# robber_v02.net
KiCad netlist of a schematic drawn in EAGLE
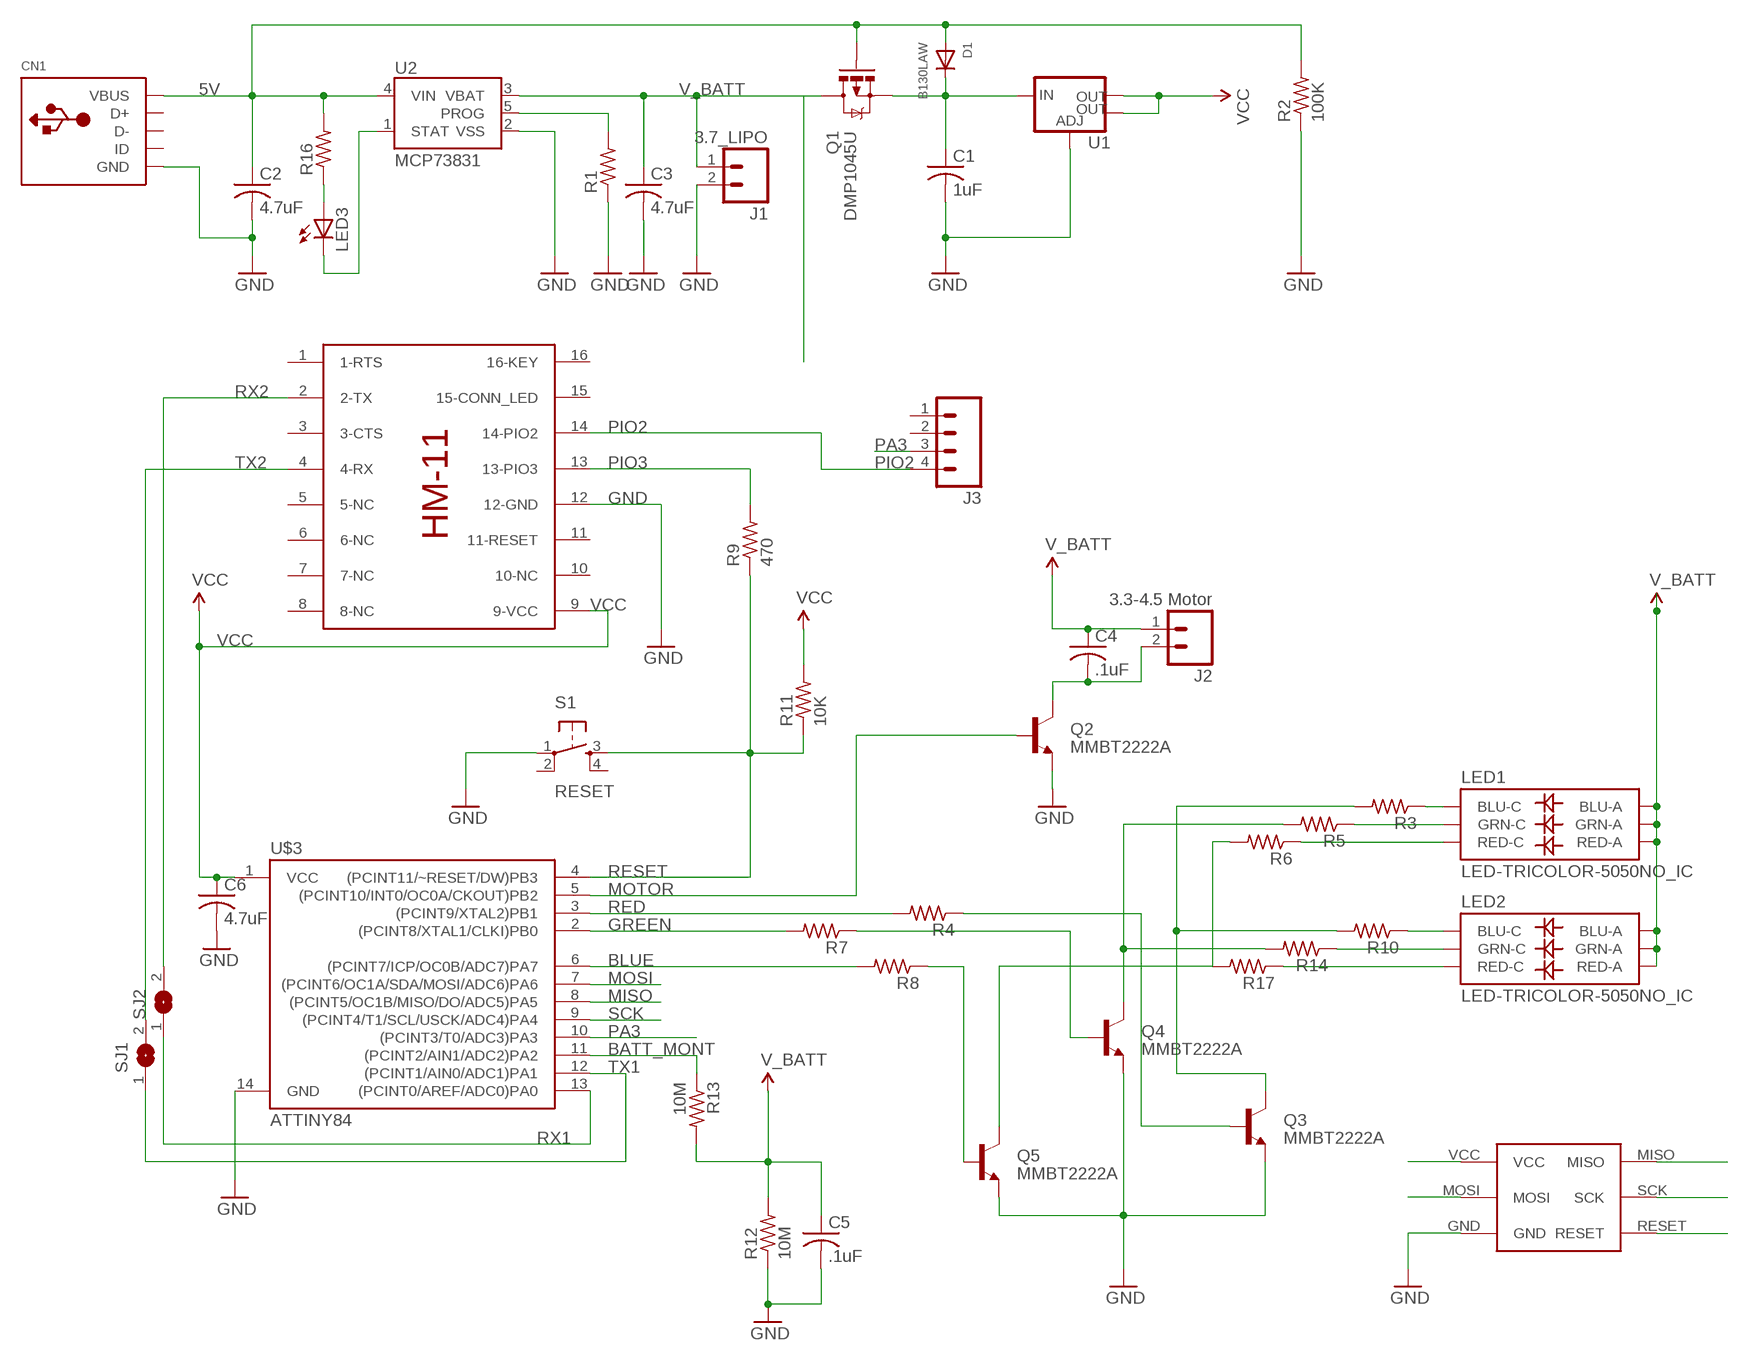
[diagram p0: schematic, sheet 1]

(export (version "E")
  (design (tool "Eeschema 10.0.6"))
  (components
    (comp (ref "C1")
      (value "1uF")
      (footprint "eagle-import:C0805K")
      (libsource (lib "eagle-import") (part "C-USC0805K"))
    )
    (comp (ref "C2")
      (value "4.7uF")
      (footprint "eagle-import:C0805K")
      (libsource (lib "eagle-import") (part "C-USC0805K"))
    )
    (comp (ref "C3")
      (value "4.7uF")
      (footprint "eagle-import:C0805")
      (libsource (lib "eagle-import") (part "C-USC0805"))
    )
    (comp (ref "C4")
      (value ".1uF")
      (footprint "eagle-import:C0402K")
      (libsource (lib "eagle-import") (part "C-USC0402K"))
    )
    (comp (ref "C5")
      (value ".1uF")
      (footprint "eagle-import:C0805")
      (libsource (lib "eagle-import") (part "C-USC0805"))
    )
    (comp (ref "C6")
      (value "4.7uF")
      (footprint "eagle-import:C0805")
      (libsource (lib "eagle-import") (part "C-USC0805"))
    )
    (comp (ref "CN1")
      (value "USBMINIB")
      (footprint "eagle-import:USB-MINIB")
      (libsource (lib "eagle-import") (part "USBMINIB"))
    )
    (comp (ref "D1")
      (value "B130LAW")
      (footprint "eagle-import:SOD-123")
      (libsource (lib "eagle-import") (part "DIODESOD-123"))
    )
    (comp (ref "J1")
      (value "3.7_LIPO")
      (footprint "eagle-import:1X02")
      (libsource (lib "eagle-import") (part "M02PTH"))
    )
    (comp (ref "J2")
      (value "3.3-4.5 Motor")
      (footprint "eagle-import:1X02")
      (libsource (lib "eagle-import") (part "M02PTH"))
    )
    (comp (ref "J3")
      (value "M04PTH")
      (footprint "eagle-import:1X04")
      (libsource (lib "eagle-import") (part "M04PTH"))
    )
    (comp (ref "LED1")
      (value "LED-TRICOLOR-5050NO_IC")
      (footprint "eagle-import:LED-TRICOLOR-5050")
      (libsource (lib "eagle-import") (part "LED-TRICOLOR-5050NO_IC"))
    )
    (comp (ref "LED2")
      (value "LED-TRICOLOR-5050NO_IC")
      (footprint "eagle-import:LED-TRICOLOR-5050")
      (libsource (lib "eagle-import") (part "LED-TRICOLOR-5050NO_IC"))
    )
    (comp (ref "LED3")
      (value "LEDSML0603")
      (footprint "eagle-import:SML0603")
      (libsource (lib "eagle-import") (part "LEDSML0603"))
    )
    (comp (ref "Q1")
      (value "DMP1045U")
      (footprint "eagle-import:SOT23-3")
      (libsource (lib "eagle-import") (part "MOSFET-PCHANNEL"))
    )
    (comp (ref "Q2")
      (value "MMBT2222A")
      (footprint "eagle-import:SOT23-3")
      (libsource (lib "eagle-import") (part "TRANSISTOR_NPNMMBT2222A"))
    )
    (comp (ref "Q3")
      (value "MMBT2222A")
      (footprint "eagle-import:SOT23-3")
      (libsource (lib "eagle-import") (part "TRANSISTOR_NPNMMBT2222A"))
    )
    (comp (ref "Q4")
      (value "MMBT2222A")
      (footprint "eagle-import:SOT23-3")
      (libsource (lib "eagle-import") (part "TRANSISTOR_NPNMMBT2222A"))
    )
    (comp (ref "Q5")
      (value "MMBT2222A")
      (footprint "eagle-import:SOT23-3")
      (libsource (lib "eagle-import") (part "TRANSISTOR_NPNMMBT2222A"))
    )
    (comp (ref "R1")
      (value "R-US_R0805W")
      (footprint "eagle-import:R0805W")
      (libsource (lib "eagle-import") (part "R-US_R0805W"))
    )
    (comp (ref "R2")
      (value "100K")
      (footprint "eagle-import:R0805W")
      (libsource (lib "eagle-import") (part "R-US_R0805W"))
    )
    (comp (ref "R3")
      (value "R-US_R0402")
      (footprint "eagle-import:R0402")
      (libsource (lib "eagle-import") (part "R-US_R0402"))
    )
    (comp (ref "R4")
      (value "R-US_R0402")
      (footprint "eagle-import:R0402")
      (libsource (lib "eagle-import") (part "R-US_R0402"))
    )
    (comp (ref "R5")
      (value "R-US_R0402")
      (footprint "eagle-import:R0402")
      (libsource (lib "eagle-import") (part "R-US_R0402"))
    )
    (comp (ref "R6")
      (value "R-US_R0402")
      (footprint "eagle-import:R0402")
      (libsource (lib "eagle-import") (part "R-US_R0402"))
    )
    (comp (ref "R7")
      (value "R-US_R0402")
      (footprint "eagle-import:R0402")
      (libsource (lib "eagle-import") (part "R-US_R0402"))
    )
    (comp (ref "R8")
      (value "R-US_R0402")
      (footprint "eagle-import:R0402")
      (libsource (lib "eagle-import") (part "R-US_R0402"))
    )
    (comp (ref "R9")
      (value "470")
      (footprint "eagle-import:R0805")
      (libsource (lib "eagle-import") (part "R-US_R0805"))
    )
    (comp (ref "R10")
      (value "R-US_R0402")
      (footprint "eagle-import:R0402")
      (libsource (lib "eagle-import") (part "R-US_R0402"))
    )
    (comp (ref "R11")
      (value "10K")
      (footprint "eagle-import:R0805W")
      (libsource (lib "eagle-import") (part "R-US_R0805W"))
    )
    (comp (ref "R12")
      (value "10M")
      (footprint "eagle-import:R0805W")
      (libsource (lib "eagle-import") (part "R-US_R0805W"))
    )
    (comp (ref "R13")
      (value "10M")
      (footprint "eagle-import:R0805W")
      (libsource (lib "eagle-import") (part "R-US_R0805W"))
    )
    (comp (ref "R14")
      (value "R-US_R0402")
      (footprint "eagle-import:R0402")
      (libsource (lib "eagle-import") (part "R-US_R0402"))
    )
    (comp (ref "R16")
      (value "R-US_R0805W")
      (footprint "eagle-import:R0805W")
      (libsource (lib "eagle-import") (part "R-US_R0805W"))
    )
    (comp (ref "R17")
      (value "R-US_R0402")
      (footprint "eagle-import:R0402")
      (libsource (lib "eagle-import") (part "R-US_R0402"))
    )
    (comp (ref "S1")
      (value "RESET")
      (footprint "eagle-import:TACTILE-SWITCH-SMD")
      (libsource (lib "eagle-import") (part "TAC_SWITCHSMD"))
    )
    (comp (ref "SJ1") (value "SJ") (footprint "eagle-import:SJ") (libsource (lib "eagle-import") (part "SJ")))
    (comp (ref "SJ2") (value "SJ") (footprint "eagle-import:SJ") (libsource (lib "eagle-import") (part "SJ")))
    (comp (ref "U$1")
      (value "HM-11")
      (footprint "eagle-import:HM-11")
      (libsource (lib "eagle-import") (part "HM-11"))
    )
    (comp (ref "U$3")
      (value "ATTINY84")
      (footprint "eagle-import:SO14")
      (libsource (lib "eagle-import") (part "ATTINY84"))
    )
    (comp (ref "U$5")
      (value "TINY-AVR-POGO-PIN-KEY")
      (footprint "eagle-import:TINY-AVR-POGO-PIN-KEY")
      (libsource (lib "eagle-import") (part "TINY-AVR-POGO-PIN-KEY"))
    )
    (comp (ref "U1")
      (value "V_REG_LM1117SOT223")
      (footprint "eagle-import:SOT223")
      (libsource (lib "eagle-import") (part "V_REG_LM1117SOT223"))
    )
    (comp (ref "U2")
      (value "MCP73831")
      (footprint "eagle-import:SOT23-5")
      (libsource (lib "eagle-import") (part "MCP73831"))
    )
  )
  (nets
    (net (code "1") (name "/5V") (class "Default")
      (node (ref "C2") (pin "1") (pinfunction "1_1") (pintype "passive"))
      (node (ref "CN1") (pin "VBUS") (pinfunction "VBUS_VBUS") (pintype "power_in"))
      (node (ref "D1") (pin "A") (pinfunction "A_A") (pintype "passive"))
      (node (ref "Q1") (pin "1") (pinfunction "G_1") (pintype "passive"))
      (node (ref "R16") (pin "2") (pinfunction "2_2") (pintype "passive"))
      (node (ref "R2") (pin "2") (pinfunction "2_2") (pintype "passive"))
      (node (ref "U2") (pin "4") (pinfunction "VIN_4") (pintype "power_in"))
    )
    (net (code "2") (name "/BATT_MONT") (class "Default")
      (node (ref "R13") (pin "1") (pinfunction "1_1") (pintype "passive"))
      (node (ref "U$3") (pin "11") (pinfunction "(PCINT2/AIN1/ADC2)PA2_11") (pintype "bidirectional"))
    )
    (net (code "3") (name "/BLUE") (class "Default")
      (node (ref "R8") (pin "2") (pinfunction "2_2") (pintype "passive"))
      (node (ref "U$3") (pin "6") (pinfunction "(PCINT7/ICP/OC0B/ADC7)PA7_6") (pintype "bidirectional"))
    )
    (net (code "4") (name "/GREEN") (class "Default")
      (node (ref "R7") (pin "2") (pinfunction "2_2") (pintype "passive"))
      (node (ref "U$3") (pin "2") (pinfunction "(PCINT8/XTAL1/CLKI)PB0_2") (pintype "bidirectional"))
    )
    (net (code "5") (name "/MISO") (class "Default")
      (node (ref "U$3") (pin "8") (pinfunction "(PCINT5/OC1B/MISO/DO/ADC5)PA5_8") (pintype "bidirectional"))
      (node (ref "U$5") (pin "MISO") (pinfunction "MISO_MISO") (pintype "bidirectional"))
    )
    (net (code "6") (name "/MOSI") (class "Default")
      (node (ref "U$3") (pin "7") (pinfunction "(PCINT6/OC1A/SDA/MOSI/ADC6)PA6_7") (pintype "bidirectional"))
      (node (ref "U$5") (pin "MOSI") (pinfunction "MOSI_MOSI") (pintype "bidirectional"))
    )
    (net (code "7") (name "/MOTOR") (class "Default")
      (node (ref "Q2") (pin "1") (pinfunction "B_1") (pintype "passive"))
      (node (ref "U$3") (pin "5") (pinfunction "(PCINT10/INT0/OC0A/CKOUT)PB2_5") (pintype "bidirectional"))
    )
    (net (code "8") (name "/PA3") (class "Default")
      (node (ref "J3") (pin "3") (pinfunction "3_3") (pintype "passive"))
      (node (ref "U$3") (pin "10") (pinfunction "(PCINT3/T0/ADC3)PA3_10") (pintype "bidirectional"))
    )
    (net (code "9") (name "/PIO2") (class "Default")
      (node (ref "J3") (pin "4") (pinfunction "4_4") (pintype "passive"))
      (node (ref "U$1") (pin "14") (pinfunction "14-PIO2_14") (pintype "bidirectional"))
    )
    (net (code "10") (name "/PIO3") (class "Default")
      (node (ref "R9") (pin "2") (pinfunction "2_2") (pintype "passive"))
      (node (ref "U$1") (pin "13") (pinfunction "13-PIO3_13") (pintype "bidirectional"))
    )
    (net (code "11") (name "/RED") (class "Default")
      (node (ref "R4") (pin "2") (pinfunction "2_2") (pintype "passive"))
      (node (ref "U$3") (pin "3") (pinfunction "(PCINT9/XTAL2)PB1_3") (pintype "bidirectional"))
    )
    (net (code "12") (name "/RESET") (class "Default")
      (node (ref "R11") (pin "1") (pinfunction "1_1") (pintype "passive"))
      (node (ref "R9") (pin "1") (pinfunction "1_1") (pintype "passive"))
      (node (ref "S1") (pin "3") (pinfunction "3_3") (pintype "passive"))
      (node (ref "U$3") (pin "4") (pinfunction "(PCINT11/~{RESET/DW})PB3_4") (pintype "bidirectional"))
      (node (ref "U$5") (pin "RESET") (pinfunction "RESET_RESET") (pintype "bidirectional"))
    )
    (net (code "13") (name "/RX1") (class "Default")
      (node (ref "SJ2") (pin "1") (pinfunction "1_1") (pintype "passive"))
      (node (ref "U$3") (pin "13") (pinfunction "(PCINT0/AREF/ADC0)PA0_13") (pintype "bidirectional"))
    )
    (net (code "14") (name "/RX2") (class "Default")
      (node (ref "SJ2") (pin "2") (pinfunction "2_2") (pintype "passive"))
      (node (ref "U$1") (pin "2") (pinfunction "2-TX_2") (pintype "bidirectional"))
    )
    (net (code "15") (name "/SCK") (class "Default")
      (node (ref "U$3") (pin "9") (pinfunction "(PCINT4/T1/SCL/USCK/ADC4)PA4_9") (pintype "bidirectional"))
      (node (ref "U$5") (pin "SCK") (pinfunction "SCK_SCK") (pintype "bidirectional"))
    )
    (net (code "16") (name "/TX1") (class "Default")
      (node (ref "SJ1") (pin "1") (pinfunction "1_1") (pintype "passive"))
      (node (ref "U$3") (pin "12") (pinfunction "(PCINT1/AIN0/ADC1)PA1_12") (pintype "bidirectional"))
    )
    (net (code "17") (name "/TX2") (class "Default")
      (node (ref "SJ1") (pin "2") (pinfunction "2_2") (pintype "passive"))
      (node (ref "U$1") (pin "4") (pinfunction "4-RX_4") (pintype "bidirectional"))
    )
    (net (code "18") (name "GND") (class "Default")
      (node (ref "C1") (pin "2") (pinfunction "2_2") (pintype "passive"))
      (node (ref "C2") (pin "2") (pinfunction "2_2") (pintype "passive"))
      (node (ref "C3") (pin "2") (pinfunction "2_2") (pintype "passive"))
      (node (ref "C5") (pin "2") (pinfunction "2_2") (pintype "passive"))
      (node (ref "C6") (pin "2") (pinfunction "2_2") (pintype "passive"))
      (node (ref "CN1") (pin "GND") (pinfunction "GND_GND") (pintype "power_in"))
      (node (ref "CN1") (pin "GND1") (pinfunction "GND_GND1") (pintype "power_in"))
      (node (ref "CN1") (pin "GND2") (pinfunction "GND_GND2") (pintype "power_in"))
      (node (ref "CN1") (pin "GND3") (pinfunction "GND_GND3") (pintype "power_in"))
      (node (ref "CN1") (pin "GND4") (pinfunction "GND_GND4") (pintype "power_in"))
      (node (ref "J1") (pin "2") (pinfunction "2_2") (pintype "passive"))
      (node (ref "Q2") (pin "2") (pinfunction "E_2") (pintype "passive"))
      (node (ref "Q3") (pin "2") (pinfunction "E_2") (pintype "passive"))
      (node (ref "Q4") (pin "2") (pinfunction "E_2") (pintype "passive"))
      (node (ref "Q5") (pin "2") (pinfunction "E_2") (pintype "passive"))
      (node (ref "R1") (pin "1") (pinfunction "1_1") (pintype "passive"))
      (node (ref "R12") (pin "1") (pinfunction "1_1") (pintype "passive"))
      (node (ref "R2") (pin "1") (pinfunction "1_1") (pintype "passive"))
      (node (ref "S1") (pin "1") (pinfunction "1_1") (pintype "passive"))
      (node (ref "U$1") (pin "12") (pinfunction "12-GND_12") (pintype "bidirectional"))
      (node (ref "U$3") (pin "14") (pinfunction "GND_14") (pintype "bidirectional"))
      (node (ref "U$5") (pin "GND") (pinfunction "GND_GND") (pintype "bidirectional"))
      (node (ref "U1") (pin "1") (pinfunction "ADJ_1") (pintype "input"))
      (node (ref "U2") (pin "2") (pinfunction "VSS_2") (pintype "power_in"))
    )
    (net (code "19") (name "Net-(LED1-BLU-C)") (class "Default")
      (node (ref "LED1") (pin "4") (pinfunction "BLU-C_4") (pintype "bidirectional"))
      (node (ref "R3") (pin "1") (pinfunction "1_1") (pintype "passive"))
    )
    (net (code "20") (name "Net-(LED1-GRN-C)") (class "Default")
      (node (ref "LED1") (pin "6") (pinfunction "GRN-C_6") (pintype "bidirectional"))
      (node (ref "R5") (pin "1") (pinfunction "1_1") (pintype "passive"))
    )
    (net (code "21") (name "Net-(LED1-RED-C)") (class "Default")
      (node (ref "LED1") (pin "5") (pinfunction "RED-C_5") (pintype "bidirectional"))
      (node (ref "R6") (pin "1") (pinfunction "1_1") (pintype "passive"))
    )
    (net (code "22") (name "Net-(LED2-BLU-C)") (class "Default")
      (node (ref "LED2") (pin "4") (pinfunction "BLU-C_4") (pintype "bidirectional"))
      (node (ref "R10") (pin "1") (pinfunction "1_1") (pintype "passive"))
    )
    (net (code "23") (name "Net-(LED2-GRN-C)") (class "Default")
      (node (ref "LED2") (pin "6") (pinfunction "GRN-C_6") (pintype "bidirectional"))
      (node (ref "R14") (pin "1") (pinfunction "1_1") (pintype "passive"))
    )
    (net (code "24") (name "Net-(LED2-RED-C)") (class "Default")
      (node (ref "LED2") (pin "5") (pinfunction "RED-C_5") (pintype "bidirectional"))
      (node (ref "R17") (pin "1") (pinfunction "1_1") (pintype "passive"))
    )
    (net (code "25") (name "Net-(LED3-PadA)") (class "Default")
      (node (ref "LED3") (pin "A") (pinfunction "A_A") (pintype "passive"))
      (node (ref "R16") (pin "1") (pinfunction "1_1") (pintype "passive"))
    )
    (net (code "26") (name "Net-(Q1-S)") (class "Default")
      (node (ref "C1") (pin "1") (pinfunction "1_1") (pintype "passive"))
      (node (ref "D1") (pin "C") (pinfunction "C_C") (pintype "passive"))
      (node (ref "Q1") (pin "2") (pinfunction "S_2") (pintype "passive"))
      (node (ref "U1") (pin "3") (pinfunction "IN_3") (pintype "input"))
    )
    (net (code "27") (name "Net-(Q2-C)") (class "Default")
      (node (ref "C4") (pin "2") (pinfunction "2_2") (pintype "passive"))
      (node (ref "J2") (pin "2") (pinfunction "2_2") (pintype "passive"))
      (node (ref "Q2") (pin "3") (pinfunction "C_3") (pintype "passive"))
    )
    (net (code "28") (name "Net-(Q3-B)") (class "Default")
      (node (ref "Q3") (pin "1") (pinfunction "B_1") (pintype "passive"))
      (node (ref "R4") (pin "1") (pinfunction "1_1") (pintype "passive"))
    )
    (net (code "29") (name "Net-(Q3-C)") (class "Default")
      (node (ref "Q3") (pin "3") (pinfunction "C_3") (pintype "passive"))
      (node (ref "R10") (pin "2") (pinfunction "2_2") (pintype "passive"))
      (node (ref "R3") (pin "2") (pinfunction "2_2") (pintype "passive"))
    )
    (net (code "30") (name "Net-(Q4-B)") (class "Default")
      (node (ref "Q4") (pin "1") (pinfunction "B_1") (pintype "passive"))
      (node (ref "R7") (pin "1") (pinfunction "1_1") (pintype "passive"))
    )
    (net (code "31") (name "Net-(Q4-C)") (class "Default")
      (node (ref "Q4") (pin "3") (pinfunction "C_3") (pintype "passive"))
      (node (ref "R14") (pin "2") (pinfunction "2_2") (pintype "passive"))
      (node (ref "R5") (pin "2") (pinfunction "2_2") (pintype "passive"))
    )
    (net (code "32") (name "Net-(Q5-B)") (class "Default")
      (node (ref "Q5") (pin "1") (pinfunction "B_1") (pintype "passive"))
      (node (ref "R8") (pin "1") (pinfunction "1_1") (pintype "passive"))
    )
    (net (code "33") (name "Net-(Q5-C)") (class "Default")
      (node (ref "Q5") (pin "3") (pinfunction "C_3") (pintype "passive"))
      (node (ref "R17") (pin "2") (pinfunction "2_2") (pintype "passive"))
      (node (ref "R6") (pin "2") (pinfunction "2_2") (pintype "passive"))
    )
    (net (code "34") (name "Net-(U2-PROG)") (class "Default")
      (node (ref "R1") (pin "2") (pinfunction "2_2") (pintype "passive"))
      (node (ref "U2") (pin "5") (pinfunction "PROG_5") (pintype "input"))
    )
    (net (code "35") (name "Net-(U2-STAT)") (class "Default")
      (node (ref "LED3") (pin "C") (pinfunction "C_C") (pintype "passive"))
      (node (ref "U2") (pin "1") (pinfunction "STAT_1") (pintype "output"))
    )
    (net (code "36") (name "VCC") (class "Default")
      (node (ref "C6") (pin "1") (pinfunction "1_1") (pintype "passive"))
      (node (ref "R11") (pin "2") (pinfunction "2_2") (pintype "passive"))
      (node (ref "U$1") (pin "9") (pinfunction "9-VCC_9") (pintype "bidirectional"))
      (node (ref "U$3") (pin "1") (pinfunction "VCC_1") (pintype "bidirectional"))
      (node (ref "U$5") (pin "VCC") (pinfunction "VCC_VCC") (pintype "bidirectional"))
      (node (ref "U1") (pin "2") (pinfunction "OUT_2") (pintype "output"))
      (node (ref "U1") (pin "4") (pinfunction "OUT_4") (pintype "output"))
    )
    (net (code "37") (name "V_BATT") (class "Default")
      (node (ref "C3") (pin "1") (pinfunction "1_1") (pintype "passive"))
      (node (ref "C4") (pin "1") (pinfunction "1_1") (pintype "passive"))
      (node (ref "C5") (pin "1") (pinfunction "1_1") (pintype "passive"))
      (node (ref "J1") (pin "1") (pinfunction "1_1") (pintype "passive"))
      (node (ref "J2") (pin "1") (pinfunction "1_1") (pintype "passive"))
      (node (ref "LED1") (pin "1") (pinfunction "GRN-A_1") (pintype "bidirectional"))
      (node (ref "LED1") (pin "2") (pinfunction "RED-A_2") (pintype "bidirectional"))
      (node (ref "LED1") (pin "3") (pinfunction "BLU-A_3") (pintype "bidirectional"))
      (node (ref "LED2") (pin "1") (pinfunction "GRN-A_1") (pintype "bidirectional"))
      (node (ref "LED2") (pin "2") (pinfunction "RED-A_2") (pintype "bidirectional"))
      (node (ref "LED2") (pin "3") (pinfunction "BLU-A_3") (pintype "bidirectional"))
      (node (ref "Q1") (pin "3") (pinfunction "D_3") (pintype "passive"))
      (node (ref "R12") (pin "2") (pinfunction "2_2") (pintype "passive"))
      (node (ref "R13") (pin "2") (pinfunction "2_2") (pintype "passive"))
      (node (ref "U2") (pin "3") (pinfunction "VBAT_3") (pintype "power_in"))
    )
    (net (code "38") (name "unconnected-(CN1-PadD+)") (class "Default")
      (node (ref "CN1") (pin "D+") (pinfunction "D+_D+") (pintype "bidirectional"))
    )
    (net (code "39") (name "unconnected-(CN1-PadD-)") (class "Default")
      (node (ref "CN1") (pin "D-") (pinfunction "D-_D-") (pintype "bidirectional"))
    )
    (net (code "40") (name "unconnected-(CN1-PadID)") (class "Default")
      (node (ref "CN1") (pin "ID") (pinfunction "ID_ID") (pintype "bidirectional"))
    )
    (net (code "41") (name "unconnected-(J3-Pad1)") (class "Default")
      (node (ref "J3") (pin "1") (pinfunction "1_1") (pintype "passive"))
    )
    (net (code "42") (name "unconnected-(J3-Pad2)") (class "Default")
      (node (ref "J3") (pin "2") (pinfunction "2_2") (pintype "passive"))
    )
    (net (code "43") (name "unconnected-(S1-Pad2)") (class "Default")
      (node (ref "S1") (pin "2") (pinfunction "2_2") (pintype "passive"))
    )
    (net (code "44") (name "unconnected-(S1-Pad4)") (class "Default")
      (node (ref "S1") (pin "4") (pinfunction "4_4") (pintype "passive"))
    )
    (net (code "45") (name "unconnected-(U$1-1-RTS-Pad1)") (class "Default")
      (node (ref "U$1") (pin "1") (pinfunction "1-RTS_1") (pintype "bidirectional"))
    )
    (net (code "46") (name "unconnected-(U$1-3-CTS-Pad3)") (class "Default")
      (node (ref "U$1") (pin "3") (pinfunction "3-CTS_3") (pintype "bidirectional"))
    )
    (net (code "47") (name "unconnected-(U$1-5-NC-Pad5)") (class "Default")
      (node (ref "U$1") (pin "5") (pinfunction "5-NC_5") (pintype "bidirectional"))
    )
    (net (code "48") (name "unconnected-(U$1-6-NC-Pad6)") (class "Default")
      (node (ref "U$1") (pin "6") (pinfunction "6-NC_6") (pintype "bidirectional"))
    )
    (net (code "49") (name "unconnected-(U$1-7-NC-Pad7)") (class "Default")
      (node (ref "U$1") (pin "7") (pinfunction "7-NC_7") (pintype "bidirectional"))
    )
    (net (code "50") (name "unconnected-(U$1-8-NC-Pad8)") (class "Default")
      (node (ref "U$1") (pin "8") (pinfunction "8-NC_8") (pintype "bidirectional"))
    )
    (net (code "51") (name "unconnected-(U$1-10-NC-Pad10)") (class "Default")
      (node (ref "U$1") (pin "10") (pinfunction "10-NC_10") (pintype "bidirectional"))
    )
    (net (code "52") (name "unconnected-(U$1-11-RESET-Pad11)") (class "Default")
      (node (ref "U$1") (pin "11") (pinfunction "11-RESET_11") (pintype "bidirectional"))
    )
    (net (code "53") (name "unconnected-(U$1-15-CONN_LED-Pad15)") (class "Default")
      (node (ref "U$1") (pin "15") (pinfunction "15-CONN_LED_15") (pintype "bidirectional"))
    )
    (net (code "54") (name "unconnected-(U$1-16-KEY-Pad16)") (class "Default")
      (node (ref "U$1") (pin "16") (pinfunction "16-KEY_16") (pintype "bidirectional"))
    )
  )
)
